# SignalFilters.net
KiCad netlist of a schematic drawn in Altium Designer
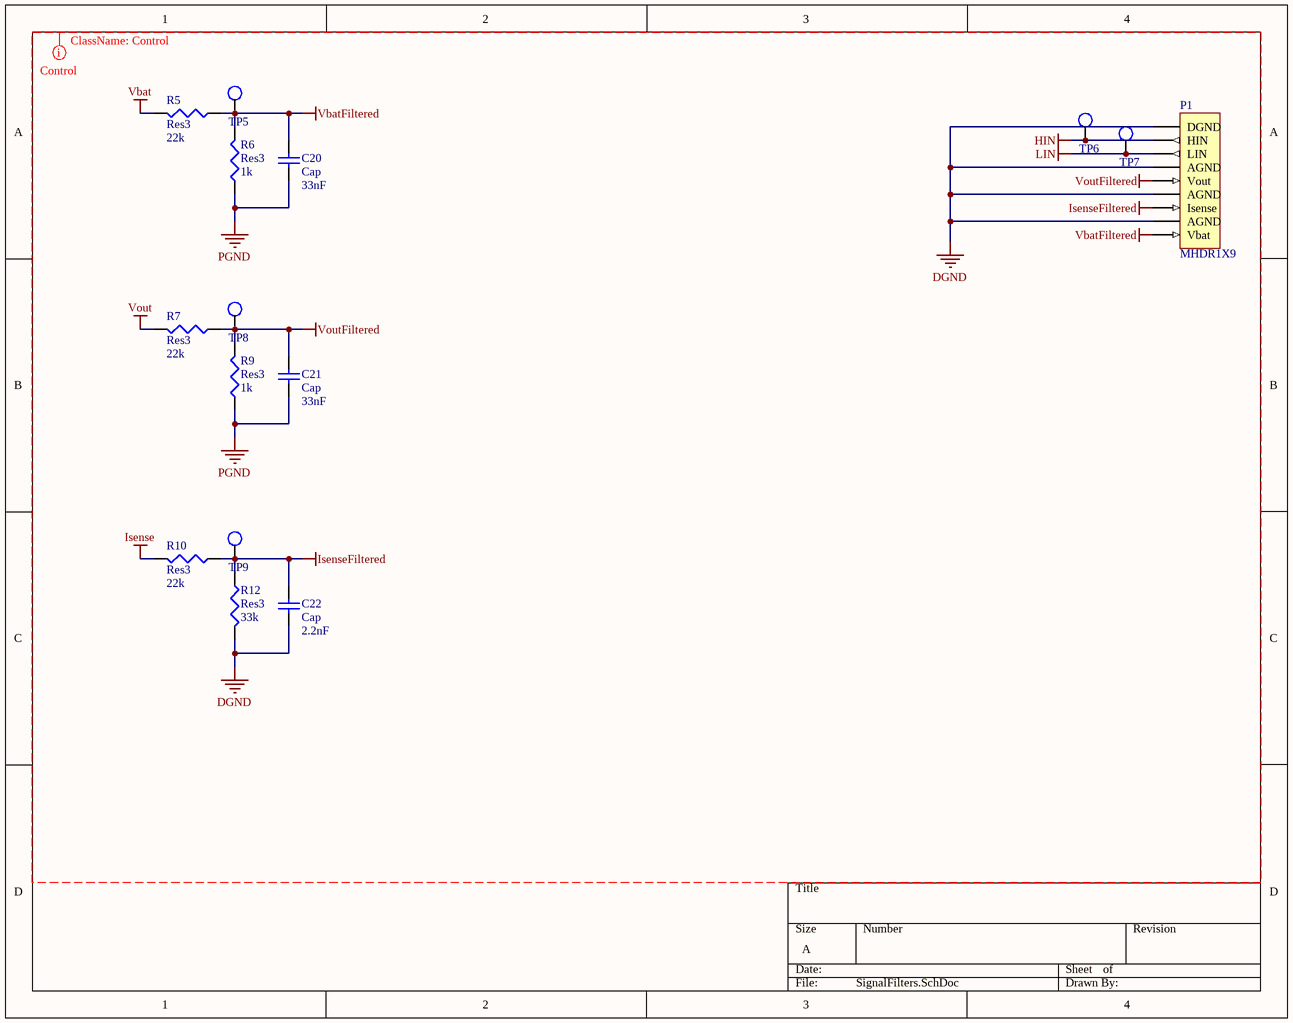
[diagram p0: SignalFilters.SchDoc]

(export (version "E")
  (design (tool "Eeschema 10.0.6"))
  (components
    (comp (ref "C20")
      (value "Cap")
      (footprint "C0603")
      (description "Capacitor")
      (fields (field (name "ALTIUM_VALUE") "33nF") (field (name "PUBLISHER") "Altium Limited"))
      (libsource (lib "Schlib1") (part "Cap"))
    )
    (comp (ref "C21")
      (value "Cap")
      (footprint "C0603")
      (description "Capacitor")
      (fields (field (name "ALTIUM_VALUE") "33nF") (field (name "PUBLISHER") "Altium Limited"))
      (libsource (lib "Schlib1") (part "Cap"))
    )
    (comp (ref "C22")
      (value "Cap")
      (footprint "C0603")
      (description "Capacitor")
      (fields (field (name "ALTIUM_VALUE") "2.2nF") (field (name "PUBLISHER") "Altium Limited"))
      (libsource (lib "Schlib1") (part "Cap"))
    )
    (comp (ref "P1")
      (value "MHDR1X9")
      (footprint "MHDR1X9")
      (description "Header, 9-Pin")
      (fields (field (name "PUBLISHER") "Altium Limited"))
      (libsource (lib "Miscellaneous Connectors") (part "MHDR1X9"))
    )
    (comp (ref "R5")
      (value "Res3")
      (footprint "J1-0603")
      (description "Resistor")
      (fields (field (name "ALTIUM_VALUE") "22k") (field (name "PUBLISHER") "Altium Limited"))
      (libsource (lib "Miscellaneous Devices") (part "Res3"))
    )
    (comp (ref "R6")
      (value "Res3")
      (footprint "J1-0603")
      (description "Resistor")
      (fields (field (name "ALTIUM_VALUE") "1k") (field (name "PUBLISHER") "Altium Limited"))
      (libsource (lib "Miscellaneous Devices") (part "Res3"))
    )
    (comp (ref "R7")
      (value "Res3")
      (footprint "J1-0603")
      (description "Resistor")
      (fields (field (name "ALTIUM_VALUE") "22k") (field (name "PUBLISHER") "Altium Limited"))
      (libsource (lib "Miscellaneous Devices") (part "Res3"))
    )
    (comp (ref "R9")
      (value "Res3")
      (footprint "J1-0603")
      (description "Resistor")
      (fields (field (name "ALTIUM_VALUE") "1k") (field (name "PUBLISHER") "Altium Limited"))
      (libsource (lib "Miscellaneous Devices") (part "Res3"))
    )
    (comp (ref "R10")
      (value "Res3")
      (footprint "J1-0603")
      (description "Resistor")
      (fields (field (name "ALTIUM_VALUE") "22k") (field (name "PUBLISHER") "Altium Limited"))
      (libsource (lib "Miscellaneous Devices") (part "Res3"))
    )
    (comp (ref "R12")
      (value "Res3")
      (footprint "J1-0603")
      (description "Resistor")
      (fields (field (name "ALTIUM_VALUE") "33k") (field (name "PUBLISHER") "Altium Limited"))
      (libsource (lib "Miscellaneous Devices") (part "Res3"))
    )
    (comp (ref "TP5")
      (value "Test Point")
      (footprint "Test Point - TH")
      (libsource (lib "Schlib1") (part "Test Point"))
    )
    (comp (ref "TP6")
      (value "Test Point")
      (footprint "Test Point - TH")
      (libsource (lib "Schlib1") (part "Test Point"))
    )
    (comp (ref "TP7")
      (value "Test Point")
      (footprint "Test Point - TH")
      (libsource (lib "Schlib1") (part "Test Point"))
    )
    (comp (ref "TP8")
      (value "Test Point")
      (footprint "Test Point - TH")
      (libsource (lib "Schlib1") (part "Test Point"))
    )
    (comp (ref "TP9")
      (value "Test Point")
      (footprint "Test Point - TH")
      (libsource (lib "Schlib1") (part "Test Point"))
    )
  )
  (nets
    (net (code "1") (name "DGND") (class "Default")
      (node (ref "C22") (pin "1") (pinfunction "1_1") (pintype "passive"))
      (node (ref "P1") (pin "1") (pinfunction "DGND_1") (pintype "passive"))
      (node (ref "P1") (pin "4") (pinfunction "AGND_4") (pintype "passive"))
      (node (ref "P1") (pin "6") (pinfunction "AGND_6") (pintype "passive"))
      (node (ref "P1") (pin "8") (pinfunction "AGND_8") (pintype "passive"))
      (node (ref "R12") (pin "2") (pinfunction "2_2") (pintype "passive"))
    )
    (net (code "2") (name "HIN") (class "Default")
      (node (ref "P1") (pin "2") (pinfunction "HIN_2") (pintype "output"))
      (node (ref "TP6") (pin "1") (pinfunction "1_1") (pintype "passive"))
    )
    (net (code "3") (name "Isense") (class "Default")
      (node (ref "R10") (pin "2") (pinfunction "2_2") (pintype "passive"))
    )
    (net (code "4") (name "IsenseFiltered") (class "Default")
      (node (ref "C22") (pin "2") (pinfunction "2_2") (pintype "passive"))
      (node (ref "P1") (pin "7") (pinfunction "Isense_7") (pintype "input"))
      (node (ref "R10") (pin "1") (pinfunction "1_1") (pintype "passive"))
      (node (ref "R12") (pin "1") (pinfunction "1_1") (pintype "passive"))
      (node (ref "TP9") (pin "1") (pinfunction "1_1") (pintype "passive"))
    )
    (net (code "5") (name "LIN") (class "Default")
      (node (ref "P1") (pin "3") (pinfunction "LIN_3") (pintype "output"))
      (node (ref "TP7") (pin "1") (pinfunction "1_1") (pintype "passive"))
    )
    (net (code "6") (name "PGND") (class "Default")
      (node (ref "C20") (pin "1") (pinfunction "1_1") (pintype "passive"))
      (node (ref "C21") (pin "1") (pinfunction "1_1") (pintype "passive"))
      (node (ref "R6") (pin "1") (pinfunction "1_1") (pintype "passive"))
      (node (ref "R9") (pin "1") (pinfunction "1_1") (pintype "passive"))
    )
    (net (code "7") (name "Vbat") (class "Default")
      (node (ref "R5") (pin "2") (pinfunction "2_2") (pintype "passive"))
    )
    (net (code "8") (name "VbatFiltered") (class "Default")
      (node (ref "C20") (pin "2") (pinfunction "2_2") (pintype "passive"))
      (node (ref "P1") (pin "9") (pinfunction "Vbat_9") (pintype "input"))
      (node (ref "R5") (pin "1") (pinfunction "1_1") (pintype "passive"))
      (node (ref "R6") (pin "2") (pinfunction "2_2") (pintype "passive"))
      (node (ref "TP5") (pin "1") (pinfunction "1_1") (pintype "passive"))
    )
    (net (code "9") (name "Vout") (class "Default")
      (node (ref "R7") (pin "2") (pinfunction "2_2") (pintype "passive"))
    )
    (net (code "10") (name "VoutFiltered") (class "Default")
      (node (ref "C21") (pin "2") (pinfunction "2_2") (pintype "passive"))
      (node (ref "P1") (pin "5") (pinfunction "Vout_5") (pintype "input"))
      (node (ref "R7") (pin "1") (pinfunction "1_1") (pintype "passive"))
      (node (ref "R9") (pin "2") (pinfunction "2_2") (pintype "passive"))
      (node (ref "TP8") (pin "1") (pinfunction "1_1") (pintype "passive"))
    )
  )
)
